# Schematic_Novek.net
KiCad netlist of a schematic drawn in EAGLE
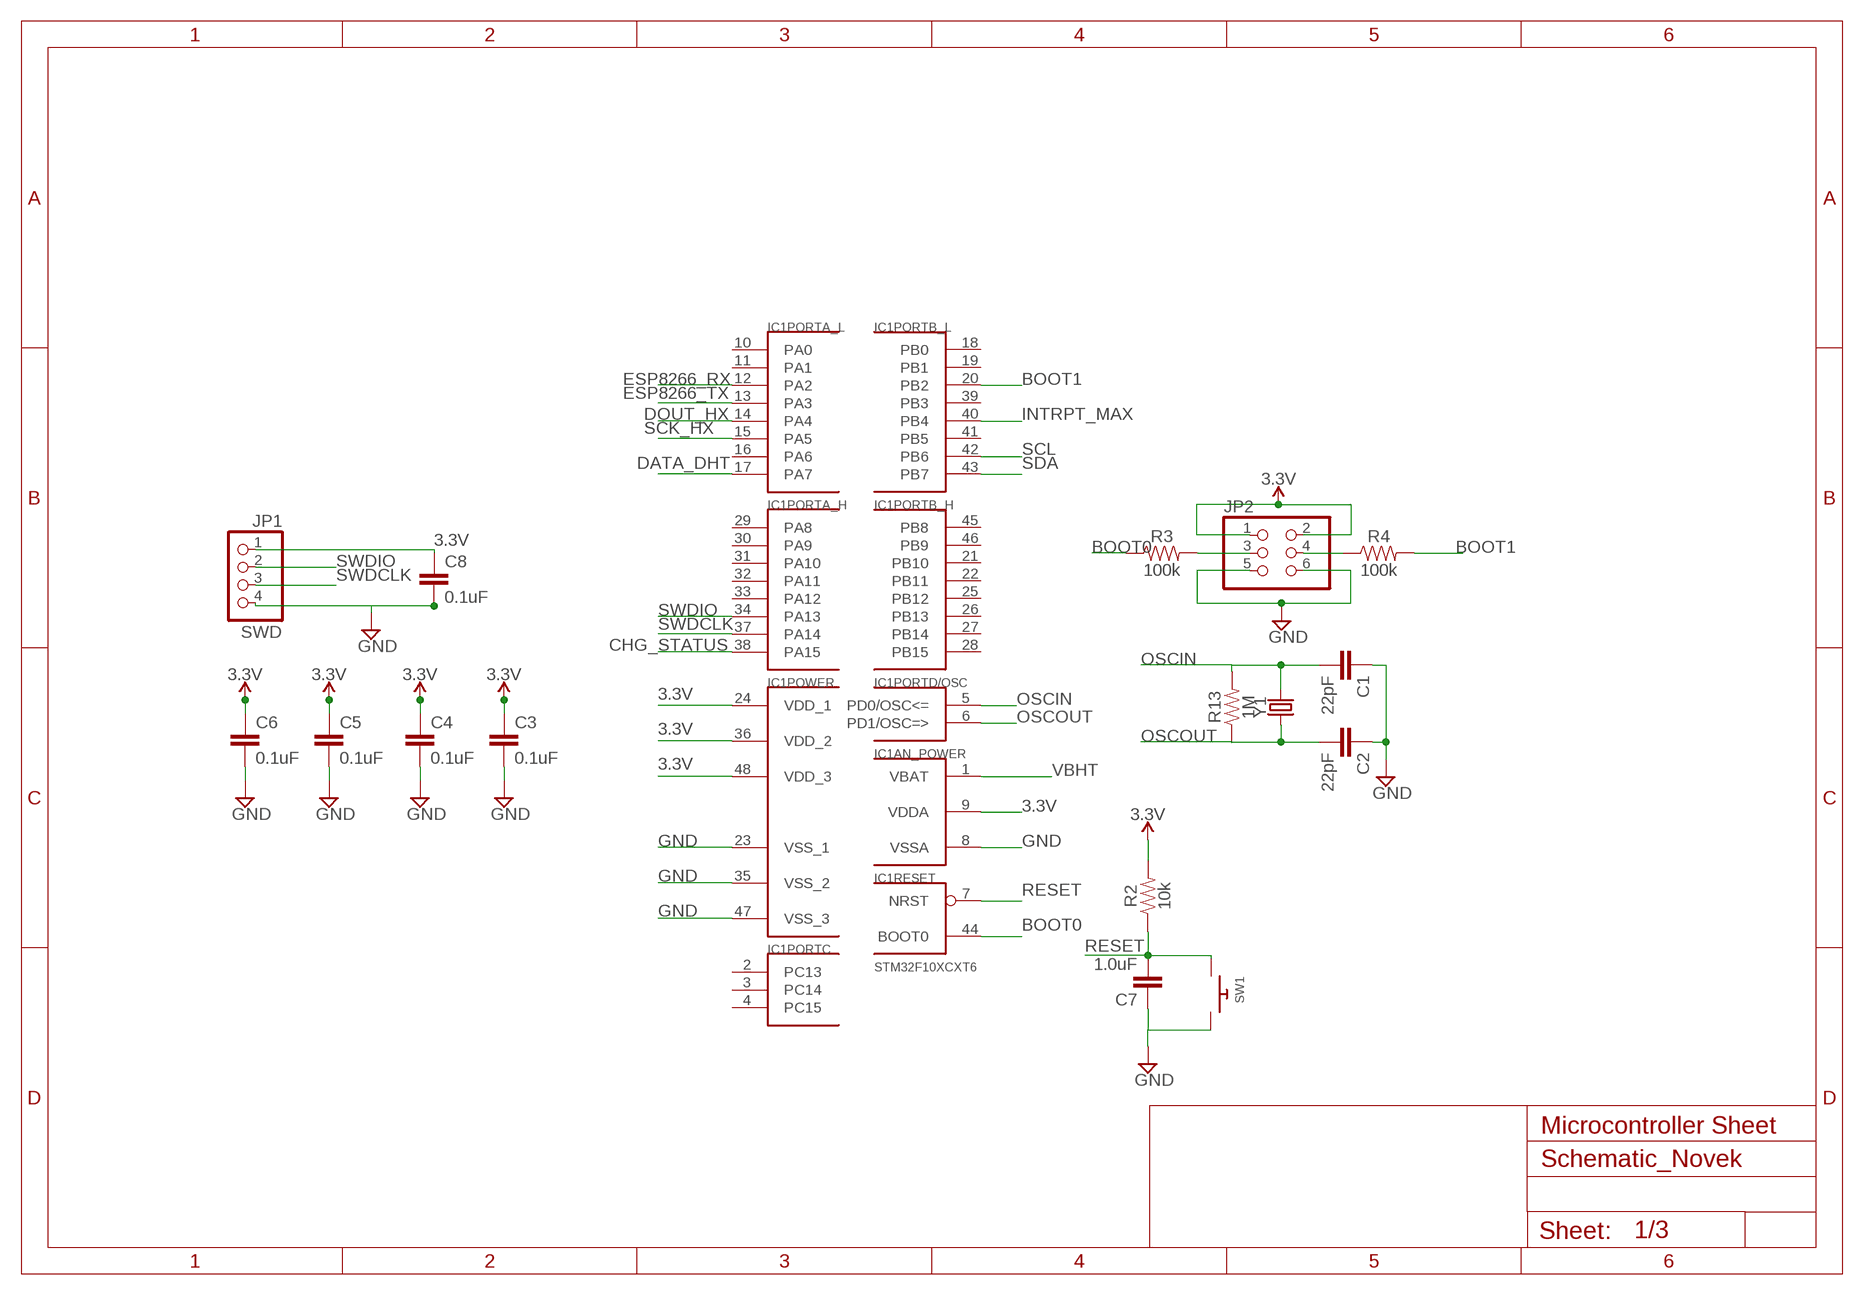
[diagram p0: schematic, sheet 1]
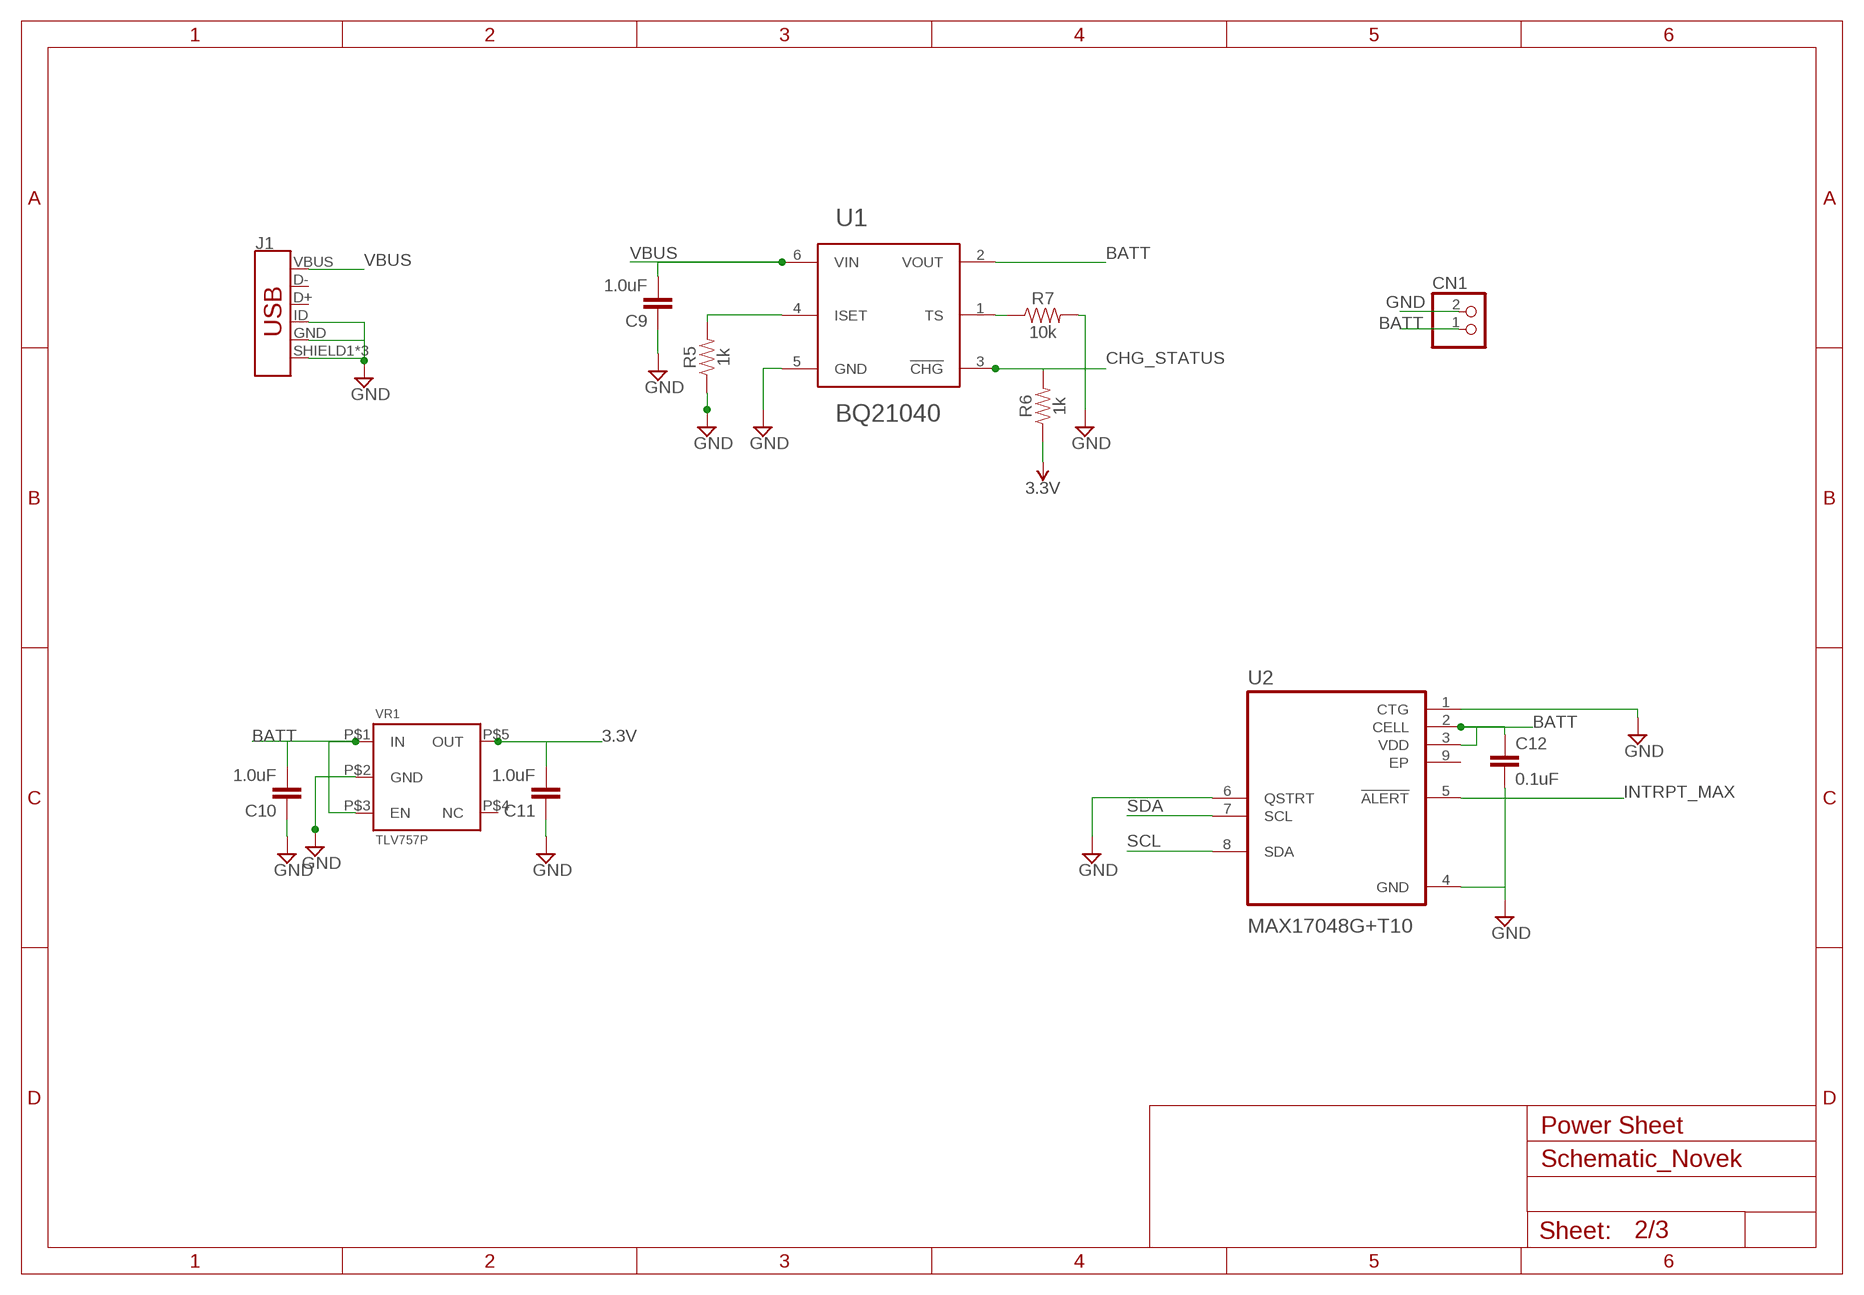
[diagram p1: schematic, sheet 2]
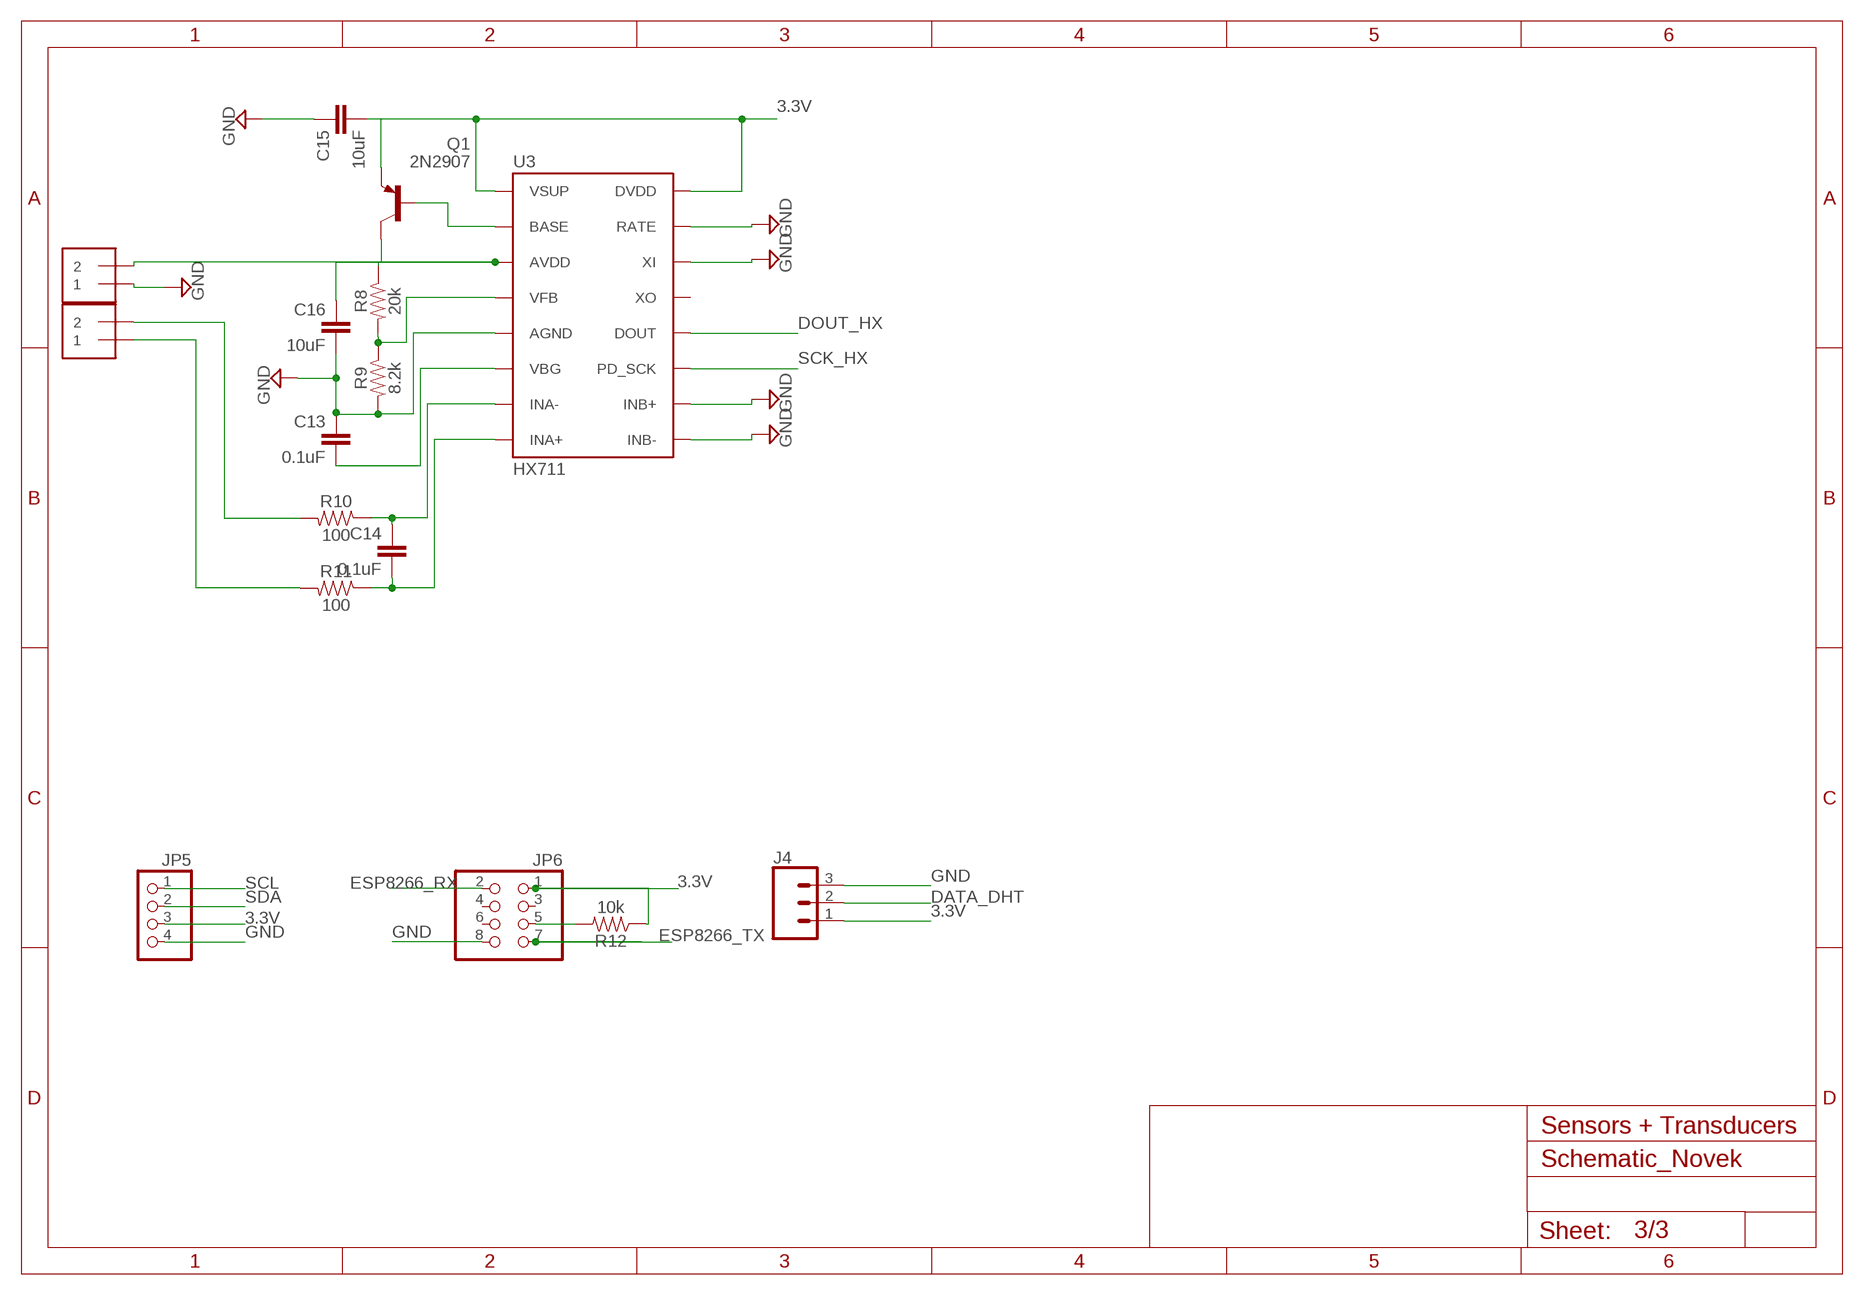
[diagram p2: schematic, sheet 3]

(export (version "E")
  (design (tool "Eeschema 10.0.6"))
  (components
    (comp (ref "C1")
      (value "22pF")
      (footprint "eagle-import:0603")
      (libsource (lib "eagle-import") (part "22PF-0603-50V-5%"))
    )
    (comp (ref "C2")
      (value "22pF")
      (footprint "eagle-import:0603")
      (libsource (lib "eagle-import") (part "22PF-0603-50V-5%"))
    )
    (comp (ref "C3")
      (value "0.1uF")
      (footprint "eagle-import:0603")
      (libsource (lib "eagle-import") (part "0.1UF-0603-25V-(+80/-20%)"))
    )
    (comp (ref "C4")
      (value "0.1uF")
      (footprint "eagle-import:0603")
      (libsource (lib "eagle-import") (part "0.1UF-0603-25V-(+80/-20%)"))
    )
    (comp (ref "C5")
      (value "0.1uF")
      (footprint "eagle-import:0603")
      (libsource (lib "eagle-import") (part "0.1UF-0603-25V-(+80/-20%)"))
    )
    (comp (ref "C6")
      (value "0.1uF")
      (footprint "eagle-import:0603")
      (libsource (lib "eagle-import") (part "0.1UF-0603-25V-(+80/-20%)"))
    )
    (comp (ref "C7")
      (value "1.0uF")
      (footprint "eagle-import:0603")
      (libsource (lib "eagle-import") (part "1.0UF-0603-16V-10%"))
    )
    (comp (ref "C8")
      (value "0.1uF")
      (footprint "eagle-import:0603")
      (libsource (lib "eagle-import") (part "0.1UF-0603-25V-(+80/-20%)"))
    )
    (comp (ref "IC1")
      (value "STM32F10XCXT6")
      (footprint "eagle-import:TQFP48")
      (libsource (lib "eagle-import") (part "STM32F10XCXT6"))
    )
    (comp (ref "JP1")
      (value "SWD")
      (footprint "eagle-import:1X04_90")
      (libsource (lib "eagle-import") (part "PINHD-1X4/90"))
    )
    (comp (ref "JP2")
      (value "PINHD-2X3")
      (footprint "eagle-import:2X03")
      (libsource (lib "eagle-import") (part "PINHD-2X3"))
    )
    (comp (ref "R2")
      (value "10k")
      (footprint "eagle-import:0603")
      (libsource (lib "eagle-import") (part "10KOHM-0603-1/10W-1%"))
    )
    (comp (ref "R3")
      (value "100k")
      (footprint "eagle-import:0603")
      (libsource (lib "eagle-import") (part "100KOHM-0603-1/10W-1%"))
    )
    (comp (ref "R4")
      (value "100k")
      (footprint "eagle-import:0603")
      (libsource (lib "eagle-import") (part "100KOHM-0603-1/10W-1%"))
    )
    (comp (ref "R13")
      (value "1M")
      (footprint "eagle-import:0603")
      (libsource (lib "eagle-import") (part "1MOHM-0603-1/4W-5%"))
    )
    (comp (ref "SW1")
      (value "SWITCH_PUSHBUTTONC&K_KSS")
      (footprint "eagle-import:BTN_CK_KSS")
      (libsource (lib "eagle-import") (part "SWITCH_PUSHBUTTONC&K_KSS"))
    )
    (comp (ref "Y1")
      (value "CRYSTALPTH-HC49UV")
      (footprint "eagle-import:HC49U")
      (libsource (lib "eagle-import") (part "CRYSTALPTH-HC49UV"))
    )
    (comp (ref "C9")
      (value "1.0uF")
      (footprint "eagle-import:0603")
      (libsource (lib "eagle-import") (part "1.0UF-0603-16V-10%"))
    )
    (comp (ref "C10")
      (value "1.0uF")
      (footprint "eagle-import:0603")
      (libsource (lib "eagle-import") (part "1.0UF-0603-16V-10%"))
    )
    (comp (ref "C11")
      (value "1.0uF")
      (footprint "eagle-import:0603")
      (libsource (lib "eagle-import") (part "1.0UF-0603-16V-10%"))
    )
    (comp (ref "C12")
      (value "0.1uF")
      (footprint "eagle-import:0603")
      (libsource (lib "eagle-import") (part "0.1UF-0603-25V-(+80/-20%)"))
    )
    (comp (ref "CN1")
      (value "JST_2PIN-THM")
      (footprint "eagle-import:JST-PH-2-THM")
      (libsource (lib "eagle-import") (part "JST_2PIN-THM"))
    )
    (comp (ref "J1")
      (value "USB_MICRO-B_FEMALE-SMT")
      (footprint "eagle-import:USB-B-MICRO-SMD")
      (libsource (lib "eagle-import") (part "USB_MICRO-B_FEMALE-SMT"))
    )
    (comp (ref "R5")
      (value "1k")
      (footprint "eagle-import:0603")
      (libsource (lib "eagle-import") (part "1KOHM-0603-1/10W-1%"))
    )
    (comp (ref "R6")
      (value "1k")
      (footprint "eagle-import:0603")
      (libsource (lib "eagle-import") (part "1KOHM-0603-1/10W-1%"))
    )
    (comp (ref "R7")
      (value "10k")
      (footprint "eagle-import:0603")
      (libsource (lib "eagle-import") (part "10KOHM-0603-1/10W-1%"))
    )
    (comp (ref "U1")
      (value "BQ21040")
      (footprint "eagle-import:SOT23-6")
      (libsource (lib "eagle-import") (part "BQ21040"))
    )
    (comp (ref "U2")
      (value "MAX17048G+T10")
      (footprint "eagle-import:SON50P200X200X80-9N")
      (fields (field (name "MF") "Maxim Integrated"))
      (libsource (lib "eagle-import") (part "MAX17048G+T10"))
    )
    (comp (ref "VR1")
      (value "TLV757P")
      (footprint "eagle-import:TLV757P")
      (fields (field (name "MF") "Texas Instruments"))
      (libsource (lib "eagle-import") (part "TLV757P"))
    )
    (comp (ref "C13")
      (value "0.1uF")
      (footprint "eagle-import:0603")
      (libsource (lib "eagle-import") (part "0.1UF-0603-25V-5%"))
    )
    (comp (ref "C14")
      (value "0.1uF")
      (footprint "eagle-import:0603")
      (libsource (lib "eagle-import") (part "0.1UF-0603-25V-5%"))
    )
    (comp (ref "C15")
      (value "10uF")
      (footprint "eagle-import:0603")
      (libsource (lib "eagle-import") (part "10UF-0603-6.3V-20%"))
    )
    (comp (ref "C16")
      (value "10uF")
      (footprint "eagle-import:0603")
      (libsource (lib "eagle-import") (part "10UF-0603-6.3V-20%"))
    )
    (comp (ref "J2")
      (value "1X2-3.5MM")
      (footprint "eagle-import:1X2-3.5MM")
      (libsource (lib "eagle-import") (part "1X2-3.5MM"))
    )
    (comp (ref "J3")
      (value "1X2-3.5MM")
      (footprint "eagle-import:1X2-3.5MM")
      (libsource (lib "eagle-import") (part "1X2-3.5MM"))
    )
    (comp (ref "J4")
      (value "CONN_03JST-PTH")
      (footprint "eagle-import:JST-3-PTH")
      (libsource (lib "eagle-import") (part "CONN_03JST-PTH"))
    )
    (comp (ref "JP5")
      (value "PINHD-1X4")
      (footprint "eagle-import:1X04")
      (libsource (lib "eagle-import") (part "PINHD-1X4"))
    )
    (comp (ref "JP6")
      (value "PINHD-2X4")
      (footprint "eagle-import:2X04")
      (libsource (lib "eagle-import") (part "PINHD-2X4"))
    )
    (comp (ref "Q1")
      (value "2N2907")
      (footprint "eagle-import:TO92-EBC-OVAL")
      (libsource (lib "eagle-import") (part "2N2907"))
    )
    (comp (ref "R8")
      (value "20k")
      (footprint "eagle-import:0603")
      (libsource (lib "eagle-import") (part "20KOHM-0603-1/10W-1%"))
    )
    (comp (ref "R9")
      (value "8.2k")
      (footprint "eagle-import:0603")
      (libsource (lib "eagle-import") (part "8.2KOHM-0603-1/10W-5%"))
    )
    (comp (ref "R10")
      (value "100")
      (footprint "eagle-import:0603")
      (libsource (lib "eagle-import") (part "100OHM-0603-1/10W-1%"))
    )
    (comp (ref "R11")
      (value "100")
      (footprint "eagle-import:0603")
      (libsource (lib "eagle-import") (part "100OHM-0603-1/10W-1%"))
    )
    (comp (ref "R12")
      (value "10k")
      (footprint "eagle-import:0603")
      (libsource (lib "eagle-import") (part "10KOHM-0603-1/10W-1%"))
    )
    (comp (ref "U3")
      (value "HX711")
      (footprint "eagle-import:SO16")
      (libsource (lib "eagle-import") (part "HX711"))
    )
  )
  (nets
    (net (code "1") (name "3.3V") (class "Default")
      (node (ref "C11") (pin "2") (pinfunction "2_2") (pintype "passive"))
      (node (ref "C15") (pin "2") (pinfunction "2_2") (pintype "passive"))
      (node (ref "C3") (pin "1") (pinfunction "1_1") (pintype "passive"))
      (node (ref "C4") (pin "1") (pinfunction "1_1") (pintype "passive"))
      (node (ref "C5") (pin "1") (pinfunction "1_1") (pintype "passive"))
      (node (ref "C6") (pin "1") (pinfunction "1_1") (pintype "passive"))
      (node (ref "C8") (pin "1") (pinfunction "1_1") (pintype "passive"))
      (node (ref "IC1") (pin "24") (pinfunction "VDD_1_24") (pintype "power_in"))
      (node (ref "IC1") (pin "36") (pinfunction "VDD_2_36") (pintype "power_in"))
      (node (ref "IC1") (pin "48") (pinfunction "VDD_3_48") (pintype "power_in"))
      (node (ref "IC1") (pin "9") (pinfunction "VDDA_9") (pintype "power_in"))
      (node (ref "J4") (pin "1") (pinfunction "1_1") (pintype "passive"))
      (node (ref "JP1") (pin "1") (pinfunction "1_1") (pintype "passive"))
      (node (ref "JP2") (pin "1") (pinfunction "1_1") (pintype "passive"))
      (node (ref "JP2") (pin "2") (pinfunction "2_2") (pintype "passive"))
      (node (ref "JP5") (pin "3") (pinfunction "3_3") (pintype "passive"))
      (node (ref "JP6") (pin "1") (pinfunction "1_1") (pintype "passive"))
      (node (ref "Q1") (pin "E") (pinfunction "E_E") (pintype "passive"))
      (node (ref "R12") (pin "1") (pinfunction "1_1") (pintype "passive"))
      (node (ref "R2") (pin "2") (pinfunction "2_2") (pintype "passive"))
      (node (ref "R6") (pin "1") (pinfunction "1_1") (pintype "passive"))
      (node (ref "U3") (pin "1") (pinfunction "VSUP_1") (pintype "bidirectional"))
      (node (ref "U3") (pin "16") (pinfunction "DVDD_16") (pintype "bidirectional"))
      (node (ref "VR1") (pin "P$5") (pinfunction "OUT_P$5") (pintype "bidirectional"))
    )
    (net (code "2") (name "BATT") (class "Default")
      (node (ref "C10") (pin "2") (pinfunction "2_2") (pintype "passive"))
      (node (ref "C12") (pin "1") (pinfunction "1_1") (pintype "passive"))
      (node (ref "CN1") (pin "1") (pinfunction "2_1") (pintype "passive"))
      (node (ref "U1") (pin "2") (pinfunction "VOUT_2") (pintype "power_in"))
      (node (ref "U2") (pin "2") (pinfunction "CELL_2") (pintype "power_in"))
      (node (ref "U2") (pin "3") (pinfunction "VDD_3") (pintype "power_in"))
      (node (ref "VR1") (pin "P$1") (pinfunction "IN_P$1") (pintype "bidirectional"))
      (node (ref "VR1") (pin "P$3") (pinfunction "EN_P$3") (pintype "bidirectional"))
    )
    (net (code "3") (name "BOOT0") (class "Default")
      (node (ref "IC1") (pin "44") (pinfunction "BOOT0_44") (pintype "input"))
      (node (ref "R3") (pin "1") (pinfunction "1_1") (pintype "passive"))
    )
    (net (code "4") (name "BOOT1") (class "Default")
      (node (ref "IC1") (pin "20") (pinfunction "PB2_20") (pintype "bidirectional"))
      (node (ref "R4") (pin "2") (pinfunction "2_2") (pintype "passive"))
    )
    (net (code "5") (name "CHG_STATUS") (class "Default")
      (node (ref "IC1") (pin "38") (pinfunction "PA15_38") (pintype "bidirectional"))
      (node (ref "R6") (pin "2") (pinfunction "2_2") (pintype "passive"))
      (node (ref "U1") (pin "3") (pinfunction "~{CHG}_3") (pintype "bidirectional"))
    )
    (net (code "6") (name "DATA_DHT") (class "Default")
      (node (ref "IC1") (pin "17") (pinfunction "PA7_17") (pintype "bidirectional"))
      (node (ref "J4") (pin "2") (pinfunction "2_2") (pintype "passive"))
    )
    (net (code "7") (name "DOUT_HX") (class "Default")
      (node (ref "IC1") (pin "14") (pinfunction "PA4_14") (pintype "bidirectional"))
      (node (ref "U3") (pin "12") (pinfunction "DOUT_12") (pintype "bidirectional"))
    )
    (net (code "8") (name "EP") (class "Default")
      (node (ref "U2") (pin "9") (pinfunction "EP_9") (pintype "power_in"))
    )
    (net (code "9") (name "ESP8266_RX") (class "Default")
      (node (ref "IC1") (pin "12") (pinfunction "PA2_12") (pintype "bidirectional"))
      (node (ref "JP6") (pin "2") (pinfunction "2_2") (pintype "passive"))
    )
    (net (code "10") (name "ESP8266_TX") (class "Default")
      (node (ref "IC1") (pin "13") (pinfunction "PA3_13") (pintype "bidirectional"))
      (node (ref "JP6") (pin "7") (pinfunction "7_7") (pintype "passive"))
    )
    (net (code "11") (name "GND") (class "Default")
      (node (ref "C1") (pin "1") (pinfunction "1_1") (pintype "passive"))
      (node (ref "C10") (pin "1") (pinfunction "1_1") (pintype "passive"))
      (node (ref "C11") (pin "1") (pinfunction "1_1") (pintype "passive"))
      (node (ref "C12") (pin "2") (pinfunction "2_2") (pintype "passive"))
      (node (ref "C13") (pin "1") (pinfunction "1_1") (pintype "passive"))
      (node (ref "C15") (pin "1") (pinfunction "1_1") (pintype "passive"))
      (node (ref "C16") (pin "2") (pinfunction "2_2") (pintype "passive"))
      (node (ref "C2") (pin "1") (pinfunction "1_1") (pintype "passive"))
      (node (ref "C3") (pin "2") (pinfunction "2_2") (pintype "passive"))
      (node (ref "C4") (pin "2") (pinfunction "2_2") (pintype "passive"))
      (node (ref "C5") (pin "2") (pinfunction "2_2") (pintype "passive"))
      (node (ref "C6") (pin "2") (pinfunction "2_2") (pintype "passive"))
      (node (ref "C7") (pin "1") (pinfunction "1_1") (pintype "passive"))
      (node (ref "C8") (pin "2") (pinfunction "2_2") (pintype "passive"))
      (node (ref "C9") (pin "1") (pinfunction "1_1") (pintype "passive"))
      (node (ref "CN1") (pin "2") (pinfunction "1_2") (pintype "passive"))
      (node (ref "IC1") (pin "23") (pinfunction "VSS_1_23") (pintype "power_in"))
      (node (ref "IC1") (pin "35") (pinfunction "VSS_2_35") (pintype "power_in"))
      (node (ref "IC1") (pin "47") (pinfunction "VSS_3_47") (pintype "power_in"))
      (node (ref "IC1") (pin "8") (pinfunction "VSSA_8") (pintype "power_in"))
      (node (ref "J1") (pin "GND") (pinfunction "GND_GND") (pintype "power_in"))
      (node (ref "J1") (pin "ID") (pinfunction "ID_ID") (pintype "bidirectional"))
      (node (ref "J1") (pin "SHIELD1") (pinfunction "SHIELD_SHIELD1") (pintype "bidirectional"))
      (node (ref "J1") (pin "SHIELD2") (pinfunction "SHIELD_SHIELD2") (pintype "bidirectional"))
      (node (ref "J1") (pin "SHIELD3") (pinfunction "SHIELD_SHIELD3") (pintype "bidirectional"))
      (node (ref "J2") (pin "1") (pinfunction "1_1") (pintype "passive"))
      (node (ref "J4") (pin "3") (pinfunction "3_3") (pintype "passive"))
      (node (ref "JP1") (pin "4") (pinfunction "4_4") (pintype "passive"))
      (node (ref "JP2") (pin "5") (pinfunction "5_5") (pintype "passive"))
      (node (ref "JP2") (pin "6") (pinfunction "6_6") (pintype "passive"))
      (node (ref "JP5") (pin "4") (pinfunction "4_4") (pintype "passive"))
      (node (ref "JP6") (pin "8") (pinfunction "8_8") (pintype "passive"))
      (node (ref "R5") (pin "1") (pinfunction "1_1") (pintype "passive"))
      (node (ref "R7") (pin "2") (pinfunction "2_2") (pintype "passive"))
      (node (ref "R9") (pin "2") (pinfunction "2_2") (pintype "passive"))
      (node (ref "SW1") (pin "P$2") (pinfunction "P$2_P$2") (pintype "passive"))
      (node (ref "U1") (pin "5") (pinfunction "GND_5") (pintype "power_in"))
      (node (ref "U2") (pin "1") (pinfunction "CTG_1") (pintype "power_in"))
      (node (ref "U2") (pin "4") (pinfunction "GND_4") (pintype "power_in"))
      (node (ref "U2") (pin "6") (pinfunction "QSTRT_6") (pintype "input"))
      (node (ref "U3") (pin "10") (pinfunction "INB+_10") (pintype "bidirectional"))
      (node (ref "U3") (pin "14") (pinfunction "XI_14") (pintype "bidirectional"))
      (node (ref "U3") (pin "15") (pinfunction "RATE_15") (pintype "bidirectional"))
      (node (ref "U3") (pin "5") (pinfunction "AGND_5") (pintype "bidirectional"))
      (node (ref "U3") (pin "9") (pinfunction "INB-_9") (pintype "bidirectional"))
      (node (ref "VR1") (pin "P$2") (pinfunction "GND_P$2") (pintype "bidirectional"))
    )
    (net (code "12") (name "INTRPT_MAX") (class "Default")
      (node (ref "IC1") (pin "40") (pinfunction "PB4_40") (pintype "bidirectional"))
      (node (ref "U2") (pin "5") (pinfunction "~{ALERT}_5") (pintype "output"))
    )
    (net (code "13") (name "Net-(J3-Pad1)") (class "Default")
      (node (ref "J3") (pin "1") (pinfunction "1_1") (pintype "passive"))
      (node (ref "R11") (pin "2") (pinfunction "2_2") (pintype "passive"))
    )
    (net (code "14") (name "Net-(J3-Pad2)") (class "Default")
      (node (ref "J3") (pin "2") (pinfunction "2_2") (pintype "passive"))
      (node (ref "R10") (pin "2") (pinfunction "2_2") (pintype "passive"))
    )
    (net (code "15") (name "Net-(JP2-Pad3)") (class "Default")
      (node (ref "JP2") (pin "3") (pinfunction "3_3") (pintype "passive"))
      (node (ref "R3") (pin "2") (pinfunction "2_2") (pintype "passive"))
    )
    (net (code "16") (name "Net-(JP2-Pad4)") (class "Default")
      (node (ref "JP2") (pin "4") (pinfunction "4_4") (pintype "passive"))
      (node (ref "R4") (pin "1") (pinfunction "1_1") (pintype "passive"))
    )
    (net (code "17") (name "Net-(JP6-Pad5)") (class "Default")
      (node (ref "JP6") (pin "5") (pinfunction "5_5") (pintype "passive"))
      (node (ref "R12") (pin "2") (pinfunction "2_2") (pintype "passive"))
    )
    (net (code "18") (name "Net-(U1-ISET)") (class "Default")
      (node (ref "R5") (pin "2") (pinfunction "2_2") (pintype "passive"))
      (node (ref "U1") (pin "4") (pinfunction "ISET_4") (pintype "bidirectional"))
    )
    (net (code "19") (name "Net-(U1-TS)") (class "Default")
      (node (ref "R7") (pin "1") (pinfunction "1_1") (pintype "passive"))
      (node (ref "U1") (pin "1") (pinfunction "TS_1") (pintype "bidirectional"))
    )
    (net (code "20") (name "Net-(U3-AVDD)") (class "Default")
      (node (ref "C16") (pin "1") (pinfunction "1_1") (pintype "passive"))
      (node (ref "J2") (pin "2") (pinfunction "2_2") (pintype "passive"))
      (node (ref "Q1") (pin "C") (pinfunction "C_C") (pintype "passive"))
      (node (ref "R8") (pin "1") (pinfunction "1_1") (pintype "passive"))
      (node (ref "U3") (pin "3") (pinfunction "AVDD_3") (pintype "bidirectional"))
    )
    (net (code "21") (name "Net-(U3-BASE)") (class "Default")
      (node (ref "Q1") (pin "B") (pinfunction "B_B") (pintype "passive"))
      (node (ref "U3") (pin "2") (pinfunction "BASE_2") (pintype "bidirectional"))
    )
    (net (code "22") (name "Net-(U3-INA+)") (class "Default")
      (node (ref "C14") (pin "2") (pinfunction "2_2") (pintype "passive"))
      (node (ref "R11") (pin "1") (pinfunction "1_1") (pintype "passive"))
      (node (ref "U3") (pin "8") (pinfunction "INA+_8") (pintype "bidirectional"))
    )
    (net (code "23") (name "Net-(U3-INA-)") (class "Default")
      (node (ref "C14") (pin "1") (pinfunction "1_1") (pintype "passive"))
      (node (ref "R10") (pin "1") (pinfunction "1_1") (pintype "passive"))
      (node (ref "U3") (pin "7") (pinfunction "INA-_7") (pintype "bidirectional"))
    )
    (net (code "24") (name "Net-(U3-VBG)") (class "Default")
      (node (ref "C13") (pin "2") (pinfunction "2_2") (pintype "passive"))
      (node (ref "U3") (pin "6") (pinfunction "VBG_6") (pintype "bidirectional"))
    )
    (net (code "25") (name "Net-(U3-VFB)") (class "Default")
      (node (ref "R8") (pin "2") (pinfunction "2_2") (pintype "passive"))
      (node (ref "R9") (pin "1") (pinfunction "1_1") (pintype "passive"))
      (node (ref "U3") (pin "4") (pinfunction "VFB_4") (pintype "bidirectional"))
    )
    (net (code "26") (name "OSCIN") (class "Default")
      (node (ref "C1") (pin "2") (pinfunction "2_2") (pintype "passive"))
      (node (ref "IC1") (pin "5") (pinfunction "PD0/OSC<=_5") (pintype "bidirectional"))
      (node (ref "R13") (pin "2") (pinfunction "2_2") (pintype "passive"))
      (node (ref "Y1") (pin "2") (pinfunction "2_2") (pintype "passive"))
    )
    (net (code "27") (name "OSCOUT") (class "Default")
      (node (ref "C2") (pin "2") (pinfunction "2_2") (pintype "passive"))
      (node (ref "IC1") (pin "6") (pinfunction "PD1/OSC=>_6") (pintype "bidirectional"))
      (node (ref "R13") (pin "1") (pinfunction "1_1") (pintype "passive"))
      (node (ref "Y1") (pin "1") (pinfunction "1_1") (pintype "passive"))
    )
    (net (code "28") (name "RESET") (class "Default")
      (node (ref "C7") (pin "2") (pinfunction "2_2") (pintype "passive"))
      (node (ref "IC1") (pin "7") (pinfunction "NRST_7") (pintype "input"))
      (node (ref "R2") (pin "1") (pinfunction "1_1") (pintype "passive"))
      (node (ref "SW1") (pin "P$1") (pinfunction "P$1_P$1") (pintype "passive"))
    )
    (net (code "29") (name "SCK_HX") (class "Default")
      (node (ref "IC1") (pin "15") (pinfunction "PA5_15") (pintype "bidirectional"))
      (node (ref "U3") (pin "11") (pinfunction "PD_SCK_11") (pintype "bidirectional"))
    )
    (net (code "30") (name "SCL") (class "Default")
      (node (ref "IC1") (pin "42") (pinfunction "PB6_42") (pintype "bidirectional"))
      (node (ref "JP5") (pin "1") (pinfunction "1_1") (pintype "passive"))
      (node (ref "U2") (pin "8") (pinfunction "SDA_8") (pintype "bidirectional"))
    )
    (net (code "31") (name "SDA") (class "Default")
      (node (ref "IC1") (pin "43") (pinfunction "PB7_43") (pintype "bidirectional"))
      (node (ref "JP5") (pin "2") (pinfunction "2_2") (pintype "passive"))
      (node (ref "U2") (pin "7") (pinfunction "SCL_7") (pintype "input"))
    )
    (net (code "32") (name "SWDCLK") (class "Default")
      (node (ref "IC1") (pin "37") (pinfunction "PA14_37") (pintype "bidirectional"))
      (node (ref "JP1") (pin "3") (pinfunction "3_3") (pintype "passive"))
    )
    (net (code "33") (name "SWDIO") (class "Default")
      (node (ref "IC1") (pin "34") (pinfunction "PA13_34") (pintype "bidirectional"))
      (node (ref "JP1") (pin "2") (pinfunction "2_2") (pintype "passive"))
    )
    (net (code "34") (name "VBHT") (class "Default")
      (node (ref "IC1") (pin "1") (pinfunction "VBAT_1") (pintype "power_in"))
    )
    (net (code "35") (name "VBUS") (class "Default")
      (node (ref "C9") (pin "2") (pinfunction "2_2") (pintype "passive"))
      (node (ref "J1") (pin "VBUS") (pinfunction "VBUS_VBUS") (pintype "power_in"))
      (node (ref "U1") (pin "6") (pinfunction "VIN_6") (pintype "power_in"))
    )
    (net (code "36") (name "unconnected-(IC1B-PA8-Pad29)") (class "Default")
      (node (ref "IC1") (pin "29") (pinfunction "PA8_29") (pintype "bidirectional"))
    )
    (net (code "37") (name "unconnected-(IC1B-PA9-Pad30)") (class "Default")
      (node (ref "IC1") (pin "30") (pinfunction "PA9_30") (pintype "bidirectional"))
    )
    (net (code "38") (name "unconnected-(IC1B-PA10-Pad31)") (class "Default")
      (node (ref "IC1") (pin "31") (pinfunction "PA10_31") (pintype "bidirectional"))
    )
    (net (code "39") (name "unconnected-(IC1B-PA11-Pad32)") (class "Default")
      (node (ref "IC1") (pin "32") (pinfunction "PA11_32") (pintype "bidirectional"))
    )
    (net (code "40") (name "unconnected-(IC1B-PA12-Pad33)") (class "Default")
      (node (ref "IC1") (pin "33") (pinfunction "PA12_33") (pintype "bidirectional"))
    )
    (net (code "41") (name "unconnected-(IC1C-PA0-Pad10)") (class "Default")
      (node (ref "IC1") (pin "10") (pinfunction "PA0_10") (pintype "bidirectional"))
    )
    (net (code "42") (name "unconnected-(IC1C-PA1-Pad11)") (class "Default")
      (node (ref "IC1") (pin "11") (pinfunction "PA1_11") (pintype "bidirectional"))
    )
    (net (code "43") (name "unconnected-(IC1C-PA6-Pad16)") (class "Default")
      (node (ref "IC1") (pin "16") (pinfunction "PA6_16") (pintype "bidirectional"))
    )
    (net (code "44") (name "unconnected-(IC1D-PB8-Pad45)") (class "Default")
      (node (ref "IC1") (pin "45") (pinfunction "PB8_45") (pintype "bidirectional"))
    )
    (net (code "45") (name "unconnected-(IC1D-PB9-Pad46)") (class "Default")
      (node (ref "IC1") (pin "46") (pinfunction "PB9_46") (pintype "bidirectional"))
    )
    (net (code "46") (name "unconnected-(IC1D-PB10-Pad21)") (class "Default")
      (node (ref "IC1") (pin "21") (pinfunction "PB10_21") (pintype "bidirectional"))
    )
    (net (code "47") (name "unconnected-(IC1D-PB11-Pad22)") (class "Default")
      (node (ref "IC1") (pin "22") (pinfunction "PB11_22") (pintype "bidirectional"))
    )
    (net (code "48") (name "unconnected-(IC1D-PB12-Pad25)") (class "Default")
      (node (ref "IC1") (pin "25") (pinfunction "PB12_25") (pintype "bidirectional"))
    )
    (net (code "49") (name "unconnected-(IC1D-PB13-Pad26)") (class "Default")
      (node (ref "IC1") (pin "26") (pinfunction "PB13_26") (pintype "bidirectional"))
    )
    (net (code "50") (name "unconnected-(IC1D-PB14-Pad27)") (class "Default")
      (node (ref "IC1") (pin "27") (pinfunction "PB14_27") (pintype "bidirectional"))
    )
    (net (code "51") (name "unconnected-(IC1D-PB15-Pad28)") (class "Default")
      (node (ref "IC1") (pin "28") (pinfunction "PB15_28") (pintype "bidirectional"))
    )
    (net (code "52") (name "unconnected-(IC1E-PB0-Pad18)") (class "Default")
      (node (ref "IC1") (pin "18") (pinfunction "PB0_18") (pintype "bidirectional"))
    )
    (net (code "53") (name "unconnected-(IC1E-PB1-Pad19)") (class "Default")
      (node (ref "IC1") (pin "19") (pinfunction "PB1_19") (pintype "bidirectional"))
    )
    (net (code "54") (name "unconnected-(IC1E-PB3-Pad39)") (class "Default")
      (node (ref "IC1") (pin "39") (pinfunction "PB3_39") (pintype "bidirectional"))
    )
    (net (code "55") (name "unconnected-(IC1E-PB5-Pad41)") (class "Default")
      (node (ref "IC1") (pin "41") (pinfunction "PB5_41") (pintype "bidirectional"))
    )
    (net (code "56") (name "unconnected-(IC1F-PC13-Pad2)") (class "Default")
      (node (ref "IC1") (pin "2") (pinfunction "PC13_2") (pintype "bidirectional"))
    )
    (net (code "57") (name "unconnected-(IC1F-PC14-Pad3)") (class "Default")
      (node (ref "IC1") (pin "3") (pinfunction "PC14_3") (pintype "bidirectional"))
    )
    (net (code "58") (name "unconnected-(IC1F-PC15-Pad4)") (class "Default")
      (node (ref "IC1") (pin "4") (pinfunction "PC15_4") (pintype "bidirectional"))
    )
    (net (code "59") (name "unconnected-(J1-PadD+)") (class "Default")
      (node (ref "J1") (pin "D+") (pinfunction "D+_D+") (pintype "bidirectional"))
    )
    (net (code "60") (name "unconnected-(J1-PadD-)") (class "Default")
      (node (ref "J1") (pin "D-") (pinfunction "D-_D-") (pintype "bidirectional"))
    )
    (net (code "61") (name "unconnected-(JP6-Pad3)") (class "Default")
      (node (ref "JP6") (pin "3") (pinfunction "3_3") (pintype "passive"))
    )
    (net (code "62") (name "unconnected-(JP6-Pad4)") (class "Default")
      (node (ref "JP6") (pin "4") (pinfunction "4_4") (pintype "passive"))
    )
    (net (code "63") (name "unconnected-(JP6-Pad6)") (class "Default")
      (node (ref "JP6") (pin "6") (pinfunction "6_6") (pintype "passive"))
    )
    (net (code "64") (name "unconnected-(U3-XO-Pad13)") (class "Default")
      (node (ref "U3") (pin "13") (pinfunction "XO_13") (pintype "bidirectional"))
    )
    (net (code "65") (name "unconnected-(VR1-NC-PadP$4)") (class "Default")
      (node (ref "VR1") (pin "P$4") (pinfunction "NC_P$4") (pintype "no_connect"))
    )
  )
)
